# CAN_Address_Switch_Array.net
KiCad netlist of a schematic drawn in Altium Designer
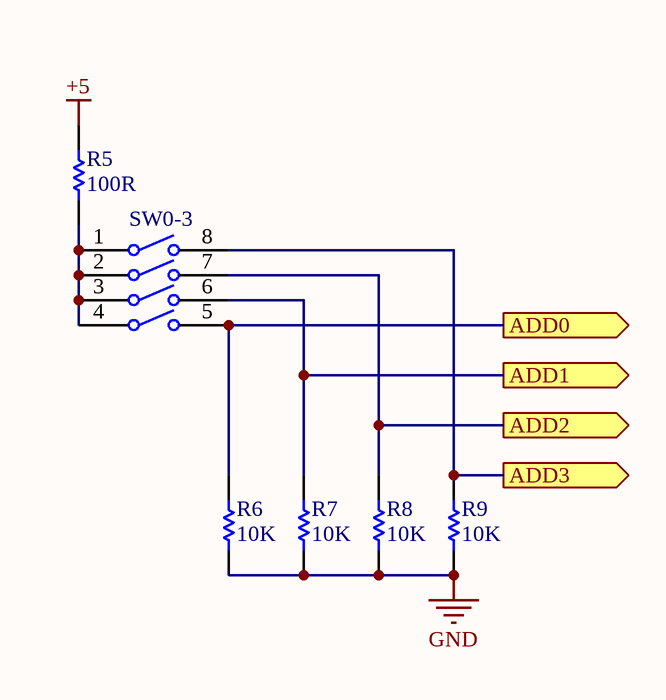
[diagram p0: CAN Address Switch Array.SchDoc]

(export (version "E")
  (design (tool "Eeschema 10.0.6"))
  (components
    (comp (ref "R5")
      (value "100R")
      (footprint "RESC0805(2012)_L")
      (description "100R 0.125W 1% 0805 (2012 Metric)  SMD")
      (fields (field (name "POWER") "0.125 W") (field (name "TOLERANCE") "1 %"))
      (libsource (lib "Altium Content Vault") (part "RES"))
    )
    (comp (ref "R6")
      (value "10K")
      (footprint "RESC0805(2012)_M")
      (description "1K 0.125W 1% 0805 (2012 Metric)  SMD")
      (fields (field (name "TOLERANCE") "1 %") (field (name "POWER") "0.125 W"))
      (libsource (lib "Altium Content Vault") (part "RES"))
    )
    (comp (ref "R7")
      (value "10K")
      (footprint "RESC0805(2012)_M")
      (description "1K 0.125W 1% 0805 (2012 Metric)  SMD")
      (fields (field (name "TOLERANCE") "1 %") (field (name "POWER") "0.125 W"))
      (libsource (lib "Altium Content Vault") (part "RES"))
    )
    (comp (ref "R8")
      (value "10K")
      (footprint "RESC0805(2012)_M")
      (description "1K 0.125W 1% 0805 (2012 Metric)  SMD")
      (fields (field (name "TOLERANCE") "1 %") (field (name "POWER") "0.125 W"))
      (libsource (lib "Altium Content Vault") (part "RES"))
    )
    (comp (ref "R9")
      (value "10K")
      (footprint "RESC0805(2012)_M")
      (description "1K 0.125W 1% 0805 (2012 Metric)  SMD")
      (fields (field (name "TOLERANCE") "1 %") (field (name "POWER") "0.125 W"))
      (libsource (lib "Altium Content Vault") (part "RES"))
    )
    (comp (ref "SW0-3")
      (value "TDA04H0SB1")
      (footprint "CKCP-TDA04H0SB1R_V")
      (libsource (lib "Husky Robotics Standard Library 2019-2020") (part "SMD Half-Pitch Dip Switch Array"))
    )
  )
  (nets
    (net (code "1") (name "+5") (class "Default")
      (node (ref "R5") (pin "2") (pinfunction "2_2") (pintype "passive"))
    )
    (net (code "2") (name "/ADD0") (class "Default")
      (node (ref "R6") (pin "2") (pinfunction "2_2") (pintype "passive"))
      (node (ref "SW0-3") (pin "5") (pinfunction "5_5") (pintype "passive"))
    )
    (net (code "3") (name "/ADD1") (class "Default")
      (node (ref "R7") (pin "2") (pinfunction "2_2") (pintype "passive"))
      (node (ref "SW0-3") (pin "6") (pinfunction "6_6") (pintype "passive"))
    )
    (net (code "4") (name "/ADD2") (class "Default")
      (node (ref "R8") (pin "2") (pinfunction "2_2") (pintype "passive"))
      (node (ref "SW0-3") (pin "7") (pinfunction "7_7") (pintype "passive"))
    )
    (net (code "5") (name "/ADD3") (class "Default")
      (node (ref "R9") (pin "2") (pinfunction "2_2") (pintype "passive"))
      (node (ref "SW0-3") (pin "8") (pinfunction "8_8") (pintype "passive"))
    )
    (net (code "6") (name "GND") (class "Default")
      (node (ref "R6") (pin "1") (pinfunction "1_1") (pintype "passive"))
      (node (ref "R7") (pin "1") (pinfunction "1_1") (pintype "passive"))
      (node (ref "R8") (pin "1") (pinfunction "1_1") (pintype "passive"))
      (node (ref "R9") (pin "1") (pinfunction "1_1") (pintype "passive"))
    )
    (net (code "7") (name "Net-(R5-Pad1)") (class "Default")
      (node (ref "R5") (pin "1") (pinfunction "1_1") (pintype "passive"))
      (node (ref "SW0-3") (pin "1") (pinfunction "1_1") (pintype "passive"))
      (node (ref "SW0-3") (pin "2") (pinfunction "2_2") (pintype "passive"))
      (node (ref "SW0-3") (pin "3") (pinfunction "3_3") (pintype "passive"))
      (node (ref "SW0-3") (pin "4") (pinfunction "4_4") (pintype "passive"))
    )
  )
)
